# deepshark_pwm_power.net
KiCad netlist of a schematic drawn in Altium Designer
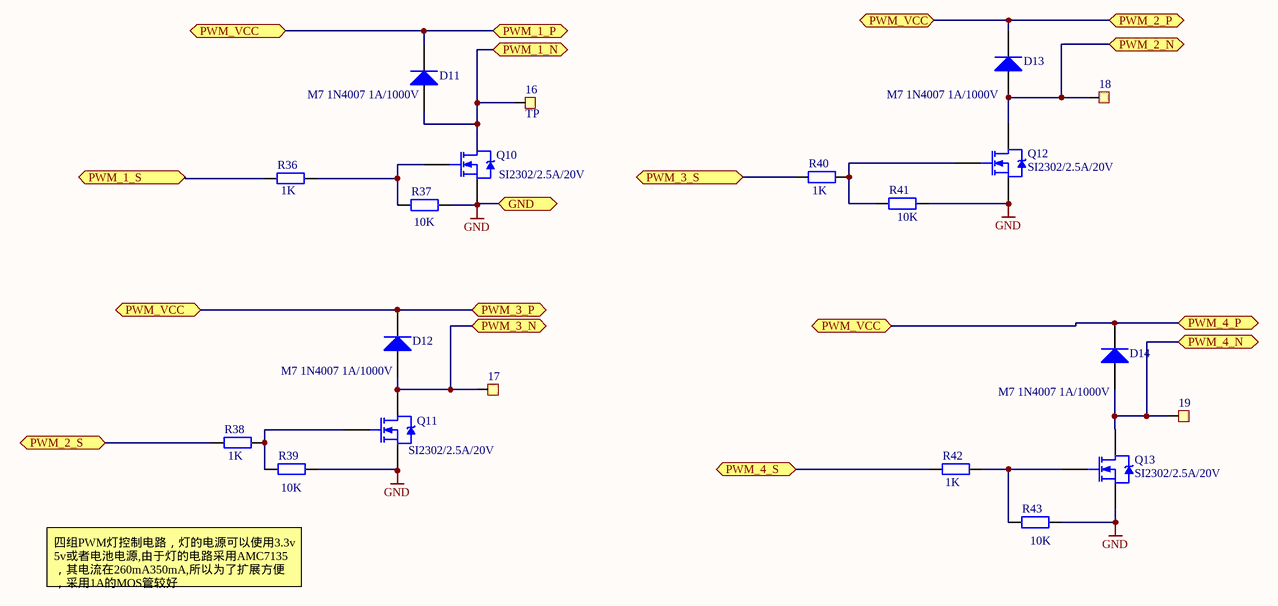
[diagram p0: deepshark_pwm_power.SchDoc]

(export (version "E")
  (design (tool "Eeschema 10.0.6"))
  (components
    (comp (ref "16") (value "TP") (footprint "TestPoint") (libsource (lib "deepshark_sch_lib") (part "TP")))
    (comp (ref "17") (value "TP") (footprint "TestPoint") (libsource (lib "deepshark_sch_lib") (part "TP")))
    (comp (ref "18") (value "TP") (footprint "TestPoint") (libsource (lib "deepshark_sch_lib") (part "TP")))
    (comp (ref "19") (value "TP") (footprint "TestPoint") (libsource (lib "deepshark_sch_lib") (part "TP")))
    (comp (ref "D11")
      (value "M7 1N4007 1A/1000V")
      (footprint "M7-1n4007")
      (description "Default Diode")
      (fields (field (name "PUBLISHER") "Altium Limited"))
      (libsource (lib "Miscellaneous Devices") (part "Diode"))
    )
    (comp (ref "D12")
      (value "M7 1N4007 1A/1000V")
      (footprint "M7-1n4007")
      (description "Default Diode")
      (fields (field (name "PUBLISHER") "Altium Limited"))
      (libsource (lib "Miscellaneous Devices") (part "Diode"))
    )
    (comp (ref "D13")
      (value "M7 1N4007 1A/1000V")
      (footprint "M7-1n4007")
      (description "Default Diode")
      (fields (field (name "PUBLISHER") "Altium Limited"))
      (libsource (lib "Miscellaneous Devices") (part "Diode"))
    )
    (comp (ref "D14")
      (value "M7 1N4007 1A/1000V")
      (footprint "M7-1n4007")
      (description "Default Diode")
      (fields (field (name "PUBLISHER") "Altium Limited"))
      (libsource (lib "Miscellaneous Devices") (part "Diode"))
    )
    (comp (ref "Q10")
      (value "SI2302/2.5A/20V")
      (footprint "SOT23_M")
      (description "N-Channel Power MOSFET")
      (fields (field (name "PUBLISHER") "Altium Limited"))
      (libsource (lib "Miscellaneous Devices") (part "NMOS-2"))
    )
    (comp (ref "Q11")
      (value "SI2302/2.5A/20V")
      (footprint "SOT23_M")
      (description "N-Channel Power MOSFET")
      (fields (field (name "PUBLISHER") "Altium Limited"))
      (libsource (lib "Miscellaneous Devices") (part "NMOS-2"))
    )
    (comp (ref "Q12")
      (value "SI2302/2.5A/20V")
      (footprint "SOT23_M")
      (description "N-Channel Power MOSFET")
      (fields (field (name "PUBLISHER") "Altium Limited"))
      (libsource (lib "Miscellaneous Devices") (part "NMOS-2"))
    )
    (comp (ref "Q13")
      (value "SI2302/2.5A/20V")
      (footprint "SOT23_M")
      (description "N-Channel Power MOSFET")
      (fields (field (name "PUBLISHER") "Altium Limited"))
      (libsource (lib "Miscellaneous Devices") (part "NMOS-2"))
    )
    (comp (ref "R36")
      (value "1K")
      (footprint "6-0805_M")
      (description "Resistor")
      (fields (field (name "Comment") "Res2") (field (name "PUBLISHER") "Altium Limited"))
      (libsource (lib "Miscellaneous Devices") (part "Res2"))
    )
    (comp (ref "R37")
      (value "10K")
      (footprint "6-0805_M")
      (description "Resistor")
      (fields (field (name "Comment") "Res2") (field (name "PUBLISHER") "Altium Limited"))
      (libsource (lib "Miscellaneous Devices") (part "Res2"))
    )
    (comp (ref "R38")
      (value "1K")
      (footprint "6-0805_M")
      (description "Resistor")
      (fields (field (name "Comment") "Res2") (field (name "PUBLISHER") "Altium Limited"))
      (libsource (lib "Miscellaneous Devices") (part "Res2"))
    )
    (comp (ref "R39")
      (value "10K")
      (footprint "6-0805_M")
      (description "Resistor")
      (fields (field (name "Comment") "Res2") (field (name "PUBLISHER") "Altium Limited"))
      (libsource (lib "Miscellaneous Devices") (part "Res2"))
    )
    (comp (ref "R40")
      (value "1K")
      (footprint "6-0805_M")
      (description "Resistor")
      (fields (field (name "Comment") "Res2") (field (name "PUBLISHER") "Altium Limited"))
      (libsource (lib "Miscellaneous Devices") (part "Res2"))
    )
    (comp (ref "R41")
      (value "10K")
      (footprint "6-0805_M")
      (description "Resistor")
      (fields (field (name "Comment") "Res2") (field (name "PUBLISHER") "Altium Limited"))
      (libsource (lib "Miscellaneous Devices") (part "Res2"))
    )
    (comp (ref "R42")
      (value "1K")
      (footprint "6-0805_M")
      (description "Resistor")
      (fields (field (name "Comment") "Res2") (field (name "PUBLISHER") "Altium Limited"))
      (libsource (lib "Miscellaneous Devices") (part "Res2"))
    )
    (comp (ref "R43")
      (value "10K")
      (footprint "6-0805_M")
      (description "Resistor")
      (fields (field (name "Comment") "Res2") (field (name "PUBLISHER") "Altium Limited"))
      (libsource (lib "Miscellaneous Devices") (part "Res2"))
    )
  )
  (nets
    (net (code "1") (name "/PWM_1_N") (class "Default")
      (node (ref "16") (pin "1") (pinfunction "1_1") (pintype "passive"))
      (node (ref "D11") (pin "1") (pinfunction "A_1") (pintype "passive"))
      (node (ref "Q10") (pin "2") (pinfunction "D_2") (pintype "passive"))
    )
    (net (code "2") (name "/PWM_1_P") (class "Default")
      (node (ref "D11") (pin "2") (pinfunction "K_2") (pintype "passive"))
      (node (ref "D12") (pin "2") (pinfunction "K_2") (pintype "passive"))
      (node (ref "D13") (pin "2") (pinfunction "K_2") (pintype "passive"))
      (node (ref "D14") (pin "2") (pinfunction "K_2") (pintype "passive"))
    )
    (net (code "3") (name "/PWM_1_S") (class "Default")
      (node (ref "R36") (pin "1") (pinfunction "1_1") (pintype "passive"))
    )
    (net (code "4") (name "/PWM_2_N") (class "Default")
      (node (ref "18") (pin "1") (pinfunction "1_1") (pintype "passive"))
      (node (ref "D13") (pin "1") (pinfunction "A_1") (pintype "passive"))
      (node (ref "Q12") (pin "2") (pinfunction "D_2") (pintype "passive"))
    )
    (net (code "5") (name "/PWM_2_S") (class "Default")
      (node (ref "R38") (pin "1") (pinfunction "1_1") (pintype "passive"))
    )
    (net (code "6") (name "/PWM_3_N") (class "Default")
      (node (ref "17") (pin "1") (pinfunction "1_1") (pintype "passive"))
      (node (ref "D12") (pin "1") (pinfunction "A_1") (pintype "passive"))
      (node (ref "Q11") (pin "2") (pinfunction "D_2") (pintype "passive"))
    )
    (net (code "7") (name "/PWM_3_S") (class "Default")
      (node (ref "R40") (pin "1") (pinfunction "1_1") (pintype "passive"))
    )
    (net (code "8") (name "/PWM_4_N") (class "Default")
      (node (ref "19") (pin "1") (pinfunction "1_1") (pintype "passive"))
      (node (ref "D14") (pin "1") (pinfunction "A_1") (pintype "passive"))
      (node (ref "Q13") (pin "2") (pinfunction "D_2") (pintype "passive"))
    )
    (net (code "9") (name "/PWM_4_S") (class "Default")
      (node (ref "R42") (pin "1") (pinfunction "1_1") (pintype "passive"))
    )
    (net (code "10") (name "GND") (class "Default")
      (node (ref "Q10") (pin "3") (pinfunction "S_3") (pintype "passive"))
      (node (ref "Q11") (pin "3") (pinfunction "S_3") (pintype "passive"))
      (node (ref "Q12") (pin "3") (pinfunction "S_3") (pintype "passive"))
      (node (ref "Q13") (pin "3") (pinfunction "S_3") (pintype "passive"))
      (node (ref "R37") (pin "2") (pinfunction "2_2") (pintype "passive"))
      (node (ref "R39") (pin "2") (pinfunction "2_2") (pintype "passive"))
      (node (ref "R41") (pin "2") (pinfunction "2_2") (pintype "passive"))
      (node (ref "R43") (pin "2") (pinfunction "2_2") (pintype "passive"))
    )
    (net (code "11") (name "Net-(Q10-G)") (class "Default")
      (node (ref "Q10") (pin "1") (pinfunction "G_1") (pintype "passive"))
      (node (ref "R36") (pin "2") (pinfunction "2_2") (pintype "passive"))
      (node (ref "R37") (pin "1") (pinfunction "1_1") (pintype "passive"))
    )
    (net (code "12") (name "Net-(Q11-G)") (class "Default")
      (node (ref "Q11") (pin "1") (pinfunction "G_1") (pintype "passive"))
      (node (ref "R38") (pin "2") (pinfunction "2_2") (pintype "passive"))
      (node (ref "R39") (pin "1") (pinfunction "1_1") (pintype "passive"))
    )
    (net (code "13") (name "Net-(Q12-G)") (class "Default")
      (node (ref "Q12") (pin "1") (pinfunction "G_1") (pintype "passive"))
      (node (ref "R40") (pin "2") (pinfunction "2_2") (pintype "passive"))
      (node (ref "R41") (pin "1") (pinfunction "1_1") (pintype "passive"))
    )
    (net (code "14") (name "Net-(Q13-G)") (class "Default")
      (node (ref "Q13") (pin "1") (pinfunction "G_1") (pintype "passive"))
      (node (ref "R42") (pin "2") (pinfunction "2_2") (pintype "passive"))
      (node (ref "R43") (pin "1") (pinfunction "1_1") (pintype "passive"))
    )
  )
)
